# SwitchModule.net
KiCad netlist of a schematic drawn in Altium Designer
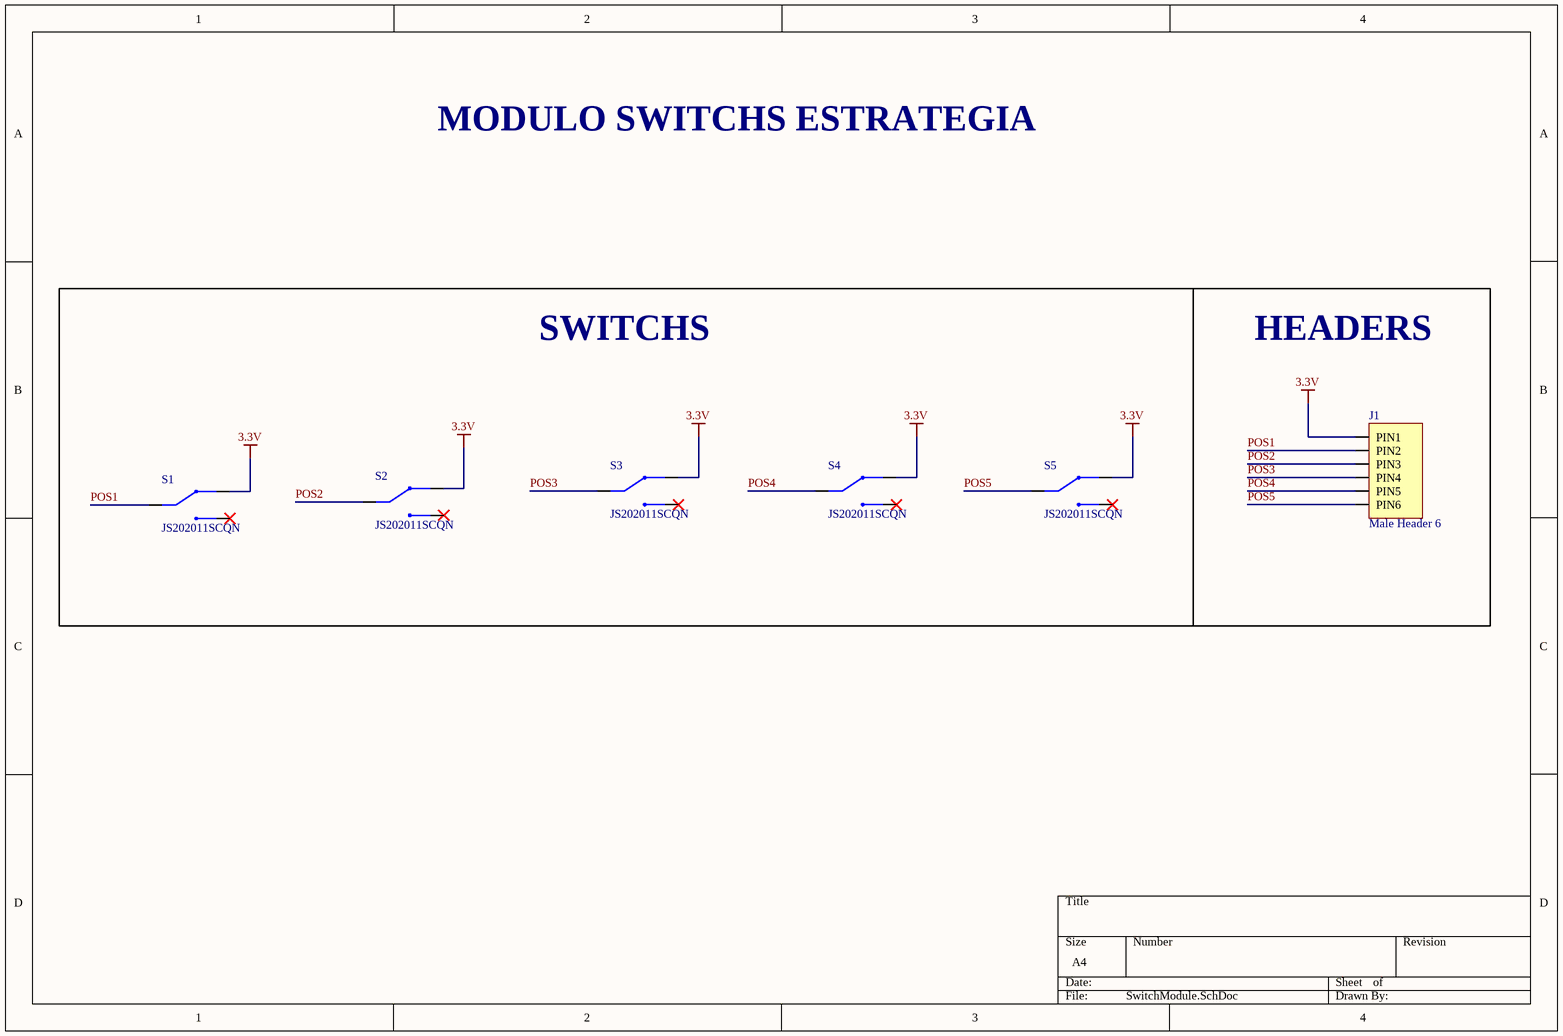
[diagram p0: SwitchModule.SchDoc]

(export (version "E")
  (design (tool "Eeschema 10.0.6"))
  (components
    (comp (ref "J1")
      (value "Male Header 6")
      (footprint "MALE HEADER 6")
      (fields
        (field (name "LIBRARY CONTROL - PERSON THAT CHECKED FOOTPRINT") "Cage")
        (field (name "LIBRARY CONTROL - PERSON THAT CHECKED SCHEMATIC") "Cage")
        (field (name "LIBRARY CONTROL - PERSON THAT DID THE LAST UPDATE SCHEMATIC") "Cage")
        (field (name "LIBRARY CONTROL - PERSONT THAT DID THE LAST UPDATE FOOTPRINT") "Cage")
      )
      (libsource (lib "Uai!Tecas") (part "Male Header 6"))
    )
    (comp (ref "S1")
      (value "JS202011SCQN")
      (footprint "DPDT")
      (description "DEEP SWITCH 4 POSITIONS")
      (fields
        (field (name "MANUFACTURER") "C&K")
        (field (name "MOUSER PART NUMBER") "611-JS202011SCQN")
        (field (name "LIBRARY CONTROL - PERSON THAT CHECKED FOOTPRINT") "Nikaum")
        (field (name "LIBRARY CONTROL - PERSON THAT CHECKED SCHEMATIC") "Nikaum")
        (field (name "LIBRARY CONTROL - PERSON THAT DID THE LAST UPDATE FOOTPRINT") "Nikaum")
        (field (name "LIBRARY CONTROL - PERSON THAT DID THE LAST UPDATE SCHEMATIC") "Nikaum")
      )
      (libsource (lib "Diversos") (part "JS202011SCQN"))
    )
    (comp (ref "S2")
      (value "JS202011SCQN")
      (footprint "DPDT")
      (description "DEEP SWITCH 4 POSITIONS")
      (fields
        (field (name "MANUFACTURER") "C&K")
        (field (name "MOUSER PART NUMBER") "611-JS202011SCQN")
        (field (name "LIBRARY CONTROL - PERSON THAT CHECKED FOOTPRINT") "Nikaum")
        (field (name "LIBRARY CONTROL - PERSON THAT CHECKED SCHEMATIC") "Nikaum")
        (field (name "LIBRARY CONTROL - PERSON THAT DID THE LAST UPDATE FOOTPRINT") "Nikaum")
        (field (name "LIBRARY CONTROL - PERSON THAT DID THE LAST UPDATE SCHEMATIC") "Nikaum")
      )
      (libsource (lib "Diversos") (part "JS202011SCQN"))
    )
    (comp (ref "S3")
      (value "JS202011SCQN")
      (footprint "DPDT")
      (description "DEEP SWITCH 4 POSITIONS")
      (fields
        (field (name "MANUFACTURER") "C&K")
        (field (name "MOUSER PART NUMBER") "611-JS202011SCQN")
        (field (name "LIBRARY CONTROL - PERSON THAT CHECKED FOOTPRINT") "Nikaum")
        (field (name "LIBRARY CONTROL - PERSON THAT CHECKED SCHEMATIC") "Nikaum")
        (field (name "LIBRARY CONTROL - PERSON THAT DID THE LAST UPDATE FOOTPRINT") "Nikaum")
        (field (name "LIBRARY CONTROL - PERSON THAT DID THE LAST UPDATE SCHEMATIC") "Nikaum")
      )
      (libsource (lib "Diversos") (part "JS202011SCQN"))
    )
    (comp (ref "S4")
      (value "JS202011SCQN")
      (footprint "DPDT")
      (description "DEEP SWITCH 4 POSITIONS")
      (fields
        (field (name "MANUFACTURER") "C&K")
        (field (name "MOUSER PART NUMBER") "611-JS202011SCQN")
        (field (name "LIBRARY CONTROL - PERSON THAT CHECKED FOOTPRINT") "Nikaum")
        (field (name "LIBRARY CONTROL - PERSON THAT CHECKED SCHEMATIC") "Nikaum")
        (field (name "LIBRARY CONTROL - PERSON THAT DID THE LAST UPDATE FOOTPRINT") "Nikaum")
        (field (name "LIBRARY CONTROL - PERSON THAT DID THE LAST UPDATE SCHEMATIC") "Nikaum")
      )
      (libsource (lib "Diversos") (part "JS202011SCQN"))
    )
    (comp (ref "S5")
      (value "JS202011SCQN")
      (footprint "DPDT")
      (description "DEEP SWITCH 4 POSITIONS")
      (fields
        (field (name "MANUFACTURER") "C&K")
        (field (name "MOUSER PART NUMBER") "611-JS202011SCQN")
        (field (name "LIBRARY CONTROL - PERSON THAT CHECKED FOOTPRINT") "Nikaum")
        (field (name "LIBRARY CONTROL - PERSON THAT CHECKED SCHEMATIC") "Nikaum")
        (field (name "LIBRARY CONTROL - PERSON THAT DID THE LAST UPDATE FOOTPRINT") "Nikaum")
        (field (name "LIBRARY CONTROL - PERSON THAT DID THE LAST UPDATE SCHEMATIC") "Nikaum")
      )
      (libsource (lib "Diversos") (part "JS202011SCQN"))
    )
  )
  (nets
    (net (code "1") (name "/POS1") (class "Default")
      (node (ref "J1") (pin "PIN2") (pinfunction "PIN2_PIN2") (pintype "passive"))
      (node (ref "S1") (pin "A1") (pinfunction "1_A1") (pintype "passive"))
    )
    (net (code "2") (name "/POS2") (class "Default")
      (node (ref "J1") (pin "PIN3") (pinfunction "PIN3_PIN3") (pintype "passive"))
      (node (ref "S2") (pin "A1") (pinfunction "1_A1") (pintype "passive"))
    )
    (net (code "3") (name "/POS3") (class "Default")
      (node (ref "J1") (pin "PIN4") (pinfunction "PIN4_PIN4") (pintype "passive"))
      (node (ref "S3") (pin "A1") (pinfunction "1_A1") (pintype "passive"))
    )
    (net (code "4") (name "/POS4") (class "Default")
      (node (ref "J1") (pin "PIN5") (pinfunction "PIN5_PIN5") (pintype "passive"))
      (node (ref "S4") (pin "A1") (pinfunction "1_A1") (pintype "passive"))
    )
    (net (code "5") (name "/POS5") (class "Default")
      (node (ref "J1") (pin "PIN6") (pinfunction "PIN6_PIN6") (pintype "passive"))
      (node (ref "S5") (pin "A1") (pinfunction "1_A1") (pintype "passive"))
    )
    (net (code "6") (name "3.3V") (class "Default")
      (node (ref "J1") (pin "PIN1") (pinfunction "PIN1_PIN1") (pintype "passive"))
      (node (ref "S1") (pin "A2") (pinfunction "4_A2") (pintype "passive"))
      (node (ref "S2") (pin "A2") (pinfunction "4_A2") (pintype "passive"))
      (node (ref "S3") (pin "A2") (pinfunction "4_A2") (pintype "passive"))
      (node (ref "S4") (pin "A2") (pinfunction "4_A2") (pintype "passive"))
      (node (ref "S5") (pin "A2") (pinfunction "4_A2") (pintype "passive"))
    )
    (net (code "7") (name "unconnected-(S1-3-PadA3)") (class "Default")
      (node (ref "S1") (pin "A3") (pinfunction "3_A3") (pintype "passive+no_connect"))
    )
    (net (code "8") (name "unconnected-(S2-3-PadA3)") (class "Default")
      (node (ref "S2") (pin "A3") (pinfunction "3_A3") (pintype "passive+no_connect"))
    )
    (net (code "9") (name "unconnected-(S3-3-PadA3)") (class "Default")
      (node (ref "S3") (pin "A3") (pinfunction "3_A3") (pintype "passive+no_connect"))
    )
    (net (code "10") (name "unconnected-(S4-3-PadA3)") (class "Default")
      (node (ref "S4") (pin "A3") (pinfunction "3_A3") (pintype "passive+no_connect"))
    )
    (net (code "11") (name "unconnected-(S5-3-PadA3)") (class "Default")
      (node (ref "S5") (pin "A3") (pinfunction "3_A3") (pintype "passive+no_connect"))
    )
  )
)
